# Decoupling.net
KiCad netlist of a schematic drawn in Altium Designer
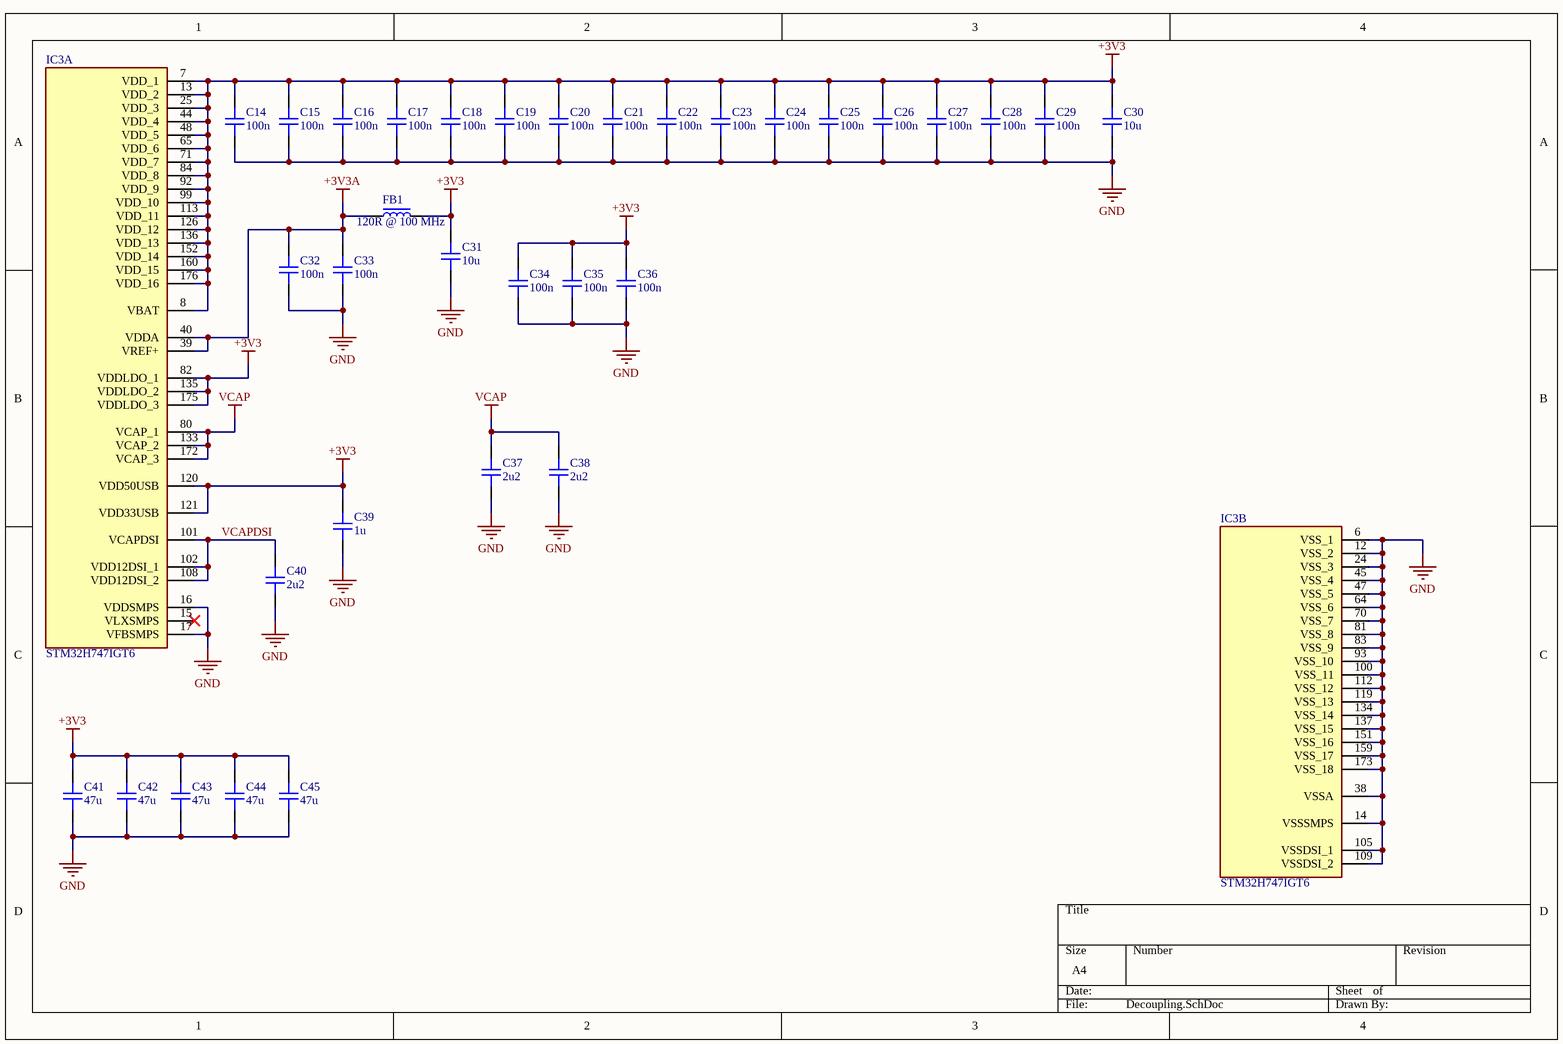
[diagram p0: Decoupling.SchDoc]

(export (version "E")
  (design (tool "Eeschema 10.0.6"))
  (components
    (comp (ref "C14")
      (value "100n")
      (footprint "CAP_0402")
      (description "Capacitor SMD 0402")
      (libsource (lib "Schematic-Lib-PhilsLab") (part "CAP_0402"))
    )
    (comp (ref "C15")
      (value "100n")
      (footprint "CAP_0402")
      (description "Capacitor SMD 0402")
      (libsource (lib "Schematic-Lib-PhilsLab") (part "CAP_0402"))
    )
    (comp (ref "C16")
      (value "100n")
      (footprint "CAP_0402")
      (description "Capacitor SMD 0402")
      (libsource (lib "Schematic-Lib-PhilsLab") (part "CAP_0402"))
    )
    (comp (ref "C17")
      (value "100n")
      (footprint "CAP_0402")
      (description "Capacitor SMD 0402")
      (libsource (lib "Schematic-Lib-PhilsLab") (part "CAP_0402"))
    )
    (comp (ref "C18")
      (value "100n")
      (footprint "CAP_0402")
      (description "Capacitor SMD 0402")
      (libsource (lib "Schematic-Lib-PhilsLab") (part "CAP_0402"))
    )
    (comp (ref "C19")
      (value "100n")
      (footprint "CAP_0402")
      (description "Capacitor SMD 0402")
      (libsource (lib "Schematic-Lib-PhilsLab") (part "CAP_0402"))
    )
    (comp (ref "C20")
      (value "100n")
      (footprint "CAP_0402")
      (description "Capacitor SMD 0402")
      (libsource (lib "Schematic-Lib-PhilsLab") (part "CAP_0402"))
    )
    (comp (ref "C21")
      (value "100n")
      (footprint "CAP_0402")
      (description "Capacitor SMD 0402")
      (libsource (lib "Schematic-Lib-PhilsLab") (part "CAP_0402"))
    )
    (comp (ref "C22")
      (value "100n")
      (footprint "CAP_0402")
      (description "Capacitor SMD 0402")
      (libsource (lib "Schematic-Lib-PhilsLab") (part "CAP_0402"))
    )
    (comp (ref "C23")
      (value "100n")
      (footprint "CAP_0402")
      (description "Capacitor SMD 0402")
      (libsource (lib "Schematic-Lib-PhilsLab") (part "CAP_0402"))
    )
    (comp (ref "C24")
      (value "100n")
      (footprint "CAP_0402")
      (description "Capacitor SMD 0402")
      (libsource (lib "Schematic-Lib-PhilsLab") (part "CAP_0402"))
    )
    (comp (ref "C25")
      (value "100n")
      (footprint "CAP_0402")
      (description "Capacitor SMD 0402")
      (libsource (lib "Schematic-Lib-PhilsLab") (part "CAP_0402"))
    )
    (comp (ref "C26")
      (value "100n")
      (footprint "CAP_0402")
      (description "Capacitor SMD 0402")
      (libsource (lib "Schematic-Lib-PhilsLab") (part "CAP_0402"))
    )
    (comp (ref "C27")
      (value "100n")
      (footprint "CAP_0402")
      (description "Capacitor SMD 0402")
      (libsource (lib "Schematic-Lib-PhilsLab") (part "CAP_0402"))
    )
    (comp (ref "C28")
      (value "100n")
      (footprint "CAP_0402")
      (description "Capacitor SMD 0402")
      (libsource (lib "Schematic-Lib-PhilsLab") (part "CAP_0402"))
    )
    (comp (ref "C29")
      (value "100n")
      (footprint "CAP_0402")
      (description "Capacitor SMD 0402")
      (libsource (lib "Schematic-Lib-PhilsLab") (part "CAP_0402"))
    )
    (comp (ref "C30")
      (value "10u")
      (footprint "CAP_0603")
      (description "Capacitor SMD 0603")
      (libsource (lib "Schematic-Lib-PhilsLab") (part "CAP_0603"))
    )
    (comp (ref "C31")
      (value "10u")
      (footprint "CAP_0603")
      (description "Capacitor SMD 0603")
      (libsource (lib "Schematic-Lib-PhilsLab") (part "CAP_0603"))
    )
    (comp (ref "C32")
      (value "100n")
      (footprint "CAP_0402")
      (description "Capacitor SMD 0402")
      (libsource (lib "Schematic-Lib-PhilsLab") (part "CAP_0402"))
    )
    (comp (ref "C33")
      (value "100n")
      (footprint "CAP_0402")
      (description "Capacitor SMD 0402")
      (libsource (lib "Schematic-Lib-PhilsLab") (part "CAP_0402"))
    )
    (comp (ref "C34")
      (value "100n")
      (footprint "CAP_0402")
      (description "Capacitor SMD 0402")
      (libsource (lib "Schematic-Lib-PhilsLab") (part "CAP_0402"))
    )
    (comp (ref "C35")
      (value "100n")
      (footprint "CAP_0402")
      (description "Capacitor SMD 0402")
      (libsource (lib "Schematic-Lib-PhilsLab") (part "CAP_0402"))
    )
    (comp (ref "C36")
      (value "100n")
      (footprint "CAP_0402")
      (description "Capacitor SMD 0402")
      (libsource (lib "Schematic-Lib-PhilsLab") (part "CAP_0402"))
    )
    (comp (ref "C37")
      (value "2u2")
      (footprint "CAP_0402")
      (description "Capacitor SMD 0402")
      (libsource (lib "Schematic-Lib-PhilsLab") (part "CAP_0402"))
    )
    (comp (ref "C38")
      (value "2u2")
      (footprint "CAP_0402")
      (description "Capacitor SMD 0402")
      (libsource (lib "Schematic-Lib-PhilsLab") (part "CAP_0402"))
    )
    (comp (ref "C39")
      (value "1u")
      (footprint "CAP_0402")
      (description "Capacitor SMD 0402")
      (libsource (lib "Schematic-Lib-PhilsLab") (part "CAP_0402"))
    )
    (comp (ref "C40")
      (value "2u2")
      (footprint "CAP_0402")
      (description "Capacitor SMD 0402")
      (libsource (lib "Schematic-Lib-PhilsLab") (part "CAP_0402"))
    )
    (comp (ref "C41")
      (value "47u")
      (footprint "CAP_1210")
      (description "Capacitor SMD 1210")
      (libsource (lib "Schematic-Lib-PhilsLab") (part "CAP_1210"))
    )
    (comp (ref "C42")
      (value "47u")
      (footprint "CAP_1210")
      (description "Capacitor SMD 1210")
      (libsource (lib "Schematic-Lib-PhilsLab") (part "CAP_1210"))
    )
    (comp (ref "C43")
      (value "47u")
      (footprint "CAP_1210")
      (description "Capacitor SMD 1210")
      (libsource (lib "Schematic-Lib-PhilsLab") (part "CAP_1210"))
    )
    (comp (ref "C44")
      (value "47u")
      (footprint "CAP_1210")
      (description "Capacitor SMD 1210")
      (libsource (lib "Schematic-Lib-PhilsLab") (part "CAP_1210"))
    )
    (comp (ref "C45")
      (value "47u")
      (footprint "CAP_1210")
      (description "Capacitor SMD 1210")
      (libsource (lib "Schematic-Lib-PhilsLab") (part "CAP_1210"))
    )
    (comp (ref "FB1")
      (value "120R @ 100 MHz")
      (footprint "FB_0402")
      (description "Ferrite Bead SMD 0402")
      (libsource (lib "Schematic-Lib-PhilsLab") (part "FB_0402"))
    )
    (comp (ref "IC3")
      (value "STM32H747IGT6")
      (footprint "Footprint-Lib-PhilsLab:QFP50P2600X2600X160-176N")
      (description "Integrated Circuit")
      (fields (field (name "MOUSER PART NUMBER") "511-STM32H747IGT6"))
      (libsource (lib "Schematic-Lib-PhilsLab") (part "STM32H747IGT6"))
    )
  )
  (nets
    (net (code "1") (name "+3V3") (class "Default")
      (node (ref "C14") (pin "2") (pinfunction "2_2") (pintype "passive"))
      (node (ref "C15") (pin "2") (pinfunction "2_2") (pintype "passive"))
      (node (ref "C16") (pin "2") (pinfunction "2_2") (pintype "passive"))
      (node (ref "C17") (pin "2") (pinfunction "2_2") (pintype "passive"))
      (node (ref "C18") (pin "2") (pinfunction "2_2") (pintype "passive"))
      (node (ref "C19") (pin "2") (pinfunction "2_2") (pintype "passive"))
      (node (ref "C20") (pin "2") (pinfunction "2_2") (pintype "passive"))
      (node (ref "C21") (pin "2") (pinfunction "2_2") (pintype "passive"))
      (node (ref "C22") (pin "2") (pinfunction "2_2") (pintype "passive"))
      (node (ref "C23") (pin "2") (pinfunction "2_2") (pintype "passive"))
      (node (ref "C24") (pin "2") (pinfunction "2_2") (pintype "passive"))
      (node (ref "C25") (pin "2") (pinfunction "2_2") (pintype "passive"))
      (node (ref "C26") (pin "2") (pinfunction "2_2") (pintype "passive"))
      (node (ref "C27") (pin "2") (pinfunction "2_2") (pintype "passive"))
      (node (ref "C28") (pin "2") (pinfunction "2_2") (pintype "passive"))
      (node (ref "C29") (pin "2") (pinfunction "2_2") (pintype "passive"))
      (node (ref "C30") (pin "2") (pinfunction "2_2") (pintype "passive"))
      (node (ref "C31") (pin "2") (pinfunction "2_2") (pintype "passive"))
      (node (ref "C34") (pin "2") (pinfunction "2_2") (pintype "passive"))
      (node (ref "C35") (pin "2") (pinfunction "2_2") (pintype "passive"))
      (node (ref "C36") (pin "2") (pinfunction "2_2") (pintype "passive"))
      (node (ref "C39") (pin "2") (pinfunction "2_2") (pintype "passive"))
      (node (ref "C41") (pin "2") (pinfunction "2_2") (pintype "passive"))
      (node (ref "C42") (pin "2") (pinfunction "2_2") (pintype "passive"))
      (node (ref "C43") (pin "2") (pinfunction "2_2") (pintype "passive"))
      (node (ref "C44") (pin "2") (pinfunction "2_2") (pintype "passive"))
      (node (ref "C45") (pin "2") (pinfunction "2_2") (pintype "passive"))
      (node (ref "FB1") (pin "2") (pinfunction "2_2") (pintype "passive"))
      (node (ref "IC3") (pin "113") (pinfunction "VDD_11_113") (pintype "passive"))
      (node (ref "IC3") (pin "120") (pinfunction "VDD50USB_120") (pintype "passive"))
      (node (ref "IC3") (pin "121") (pinfunction "VDD33USB_121") (pintype "passive"))
      (node (ref "IC3") (pin "126") (pinfunction "VDD_12_126") (pintype "passive"))
      (node (ref "IC3") (pin "13") (pinfunction "VDD_2_13") (pintype "passive"))
      (node (ref "IC3") (pin "135") (pinfunction "VDDLDO_2_135") (pintype "passive"))
      (node (ref "IC3") (pin "136") (pinfunction "VDD_13_136") (pintype "passive"))
      (node (ref "IC3") (pin "152") (pinfunction "VDD_14_152") (pintype "passive"))
      (node (ref "IC3") (pin "160") (pinfunction "VDD_15_160") (pintype "passive"))
      (node (ref "IC3") (pin "175") (pinfunction "VDDLDO_3_175") (pintype "passive"))
      (node (ref "IC3") (pin "176") (pinfunction "VDD_16_176") (pintype "passive"))
      (node (ref "IC3") (pin "25") (pinfunction "VDD_3_25") (pintype "passive"))
      (node (ref "IC3") (pin "44") (pinfunction "VDD_4_44") (pintype "passive"))
      (node (ref "IC3") (pin "48") (pinfunction "VDD_5_48") (pintype "passive"))
      (node (ref "IC3") (pin "65") (pinfunction "VDD_6_65") (pintype "passive"))
      (node (ref "IC3") (pin "7") (pinfunction "VDD_1_7") (pintype "passive"))
      (node (ref "IC3") (pin "71") (pinfunction "VDD_7_71") (pintype "passive"))
      (node (ref "IC3") (pin "8") (pinfunction "VBAT_8") (pintype "passive"))
      (node (ref "IC3") (pin "82") (pinfunction "VDDLDO_1_82") (pintype "passive"))
      (node (ref "IC3") (pin "84") (pinfunction "VDD_8_84") (pintype "passive"))
      (node (ref "IC3") (pin "92") (pinfunction "VDD_9_92") (pintype "passive"))
      (node (ref "IC3") (pin "99") (pinfunction "VDD_10_99") (pintype "passive"))
    )
    (net (code "2") (name "+3V3A") (class "Default")
      (node (ref "C32") (pin "2") (pinfunction "2_2") (pintype "passive"))
      (node (ref "C33") (pin "2") (pinfunction "2_2") (pintype "passive"))
      (node (ref "FB1") (pin "1") (pinfunction "1_1") (pintype "passive"))
      (node (ref "IC3") (pin "39") (pinfunction "VREF+_39") (pintype "passive"))
      (node (ref "IC3") (pin "40") (pinfunction "VDDA_40") (pintype "passive"))
    )
    (net (code "3") (name "/VCAPDSI") (class "Default")
      (node (ref "C40") (pin "2") (pinfunction "2_2") (pintype "passive"))
      (node (ref "IC3") (pin "101") (pinfunction "VCAPDSI_101") (pintype "passive"))
      (node (ref "IC3") (pin "102") (pinfunction "VDD12DSI_1_102") (pintype "passive"))
      (node (ref "IC3") (pin "108") (pinfunction "VDD12DSI_2_108") (pintype "passive"))
    )
    (net (code "4") (name "GND") (class "Default")
      (node (ref "C14") (pin "1") (pinfunction "1_1") (pintype "passive"))
      (node (ref "C15") (pin "1") (pinfunction "1_1") (pintype "passive"))
      (node (ref "C16") (pin "1") (pinfunction "1_1") (pintype "passive"))
      (node (ref "C17") (pin "1") (pinfunction "1_1") (pintype "passive"))
      (node (ref "C18") (pin "1") (pinfunction "1_1") (pintype "passive"))
      (node (ref "C19") (pin "1") (pinfunction "1_1") (pintype "passive"))
      (node (ref "C20") (pin "1") (pinfunction "1_1") (pintype "passive"))
      (node (ref "C21") (pin "1") (pinfunction "1_1") (pintype "passive"))
      (node (ref "C22") (pin "1") (pinfunction "1_1") (pintype "passive"))
      (node (ref "C23") (pin "1") (pinfunction "1_1") (pintype "passive"))
      (node (ref "C24") (pin "1") (pinfunction "1_1") (pintype "passive"))
      (node (ref "C25") (pin "1") (pinfunction "1_1") (pintype "passive"))
      (node (ref "C26") (pin "1") (pinfunction "1_1") (pintype "passive"))
      (node (ref "C27") (pin "1") (pinfunction "1_1") (pintype "passive"))
      (node (ref "C28") (pin "1") (pinfunction "1_1") (pintype "passive"))
      (node (ref "C29") (pin "1") (pinfunction "1_1") (pintype "passive"))
      (node (ref "C30") (pin "1") (pinfunction "1_1") (pintype "passive"))
      (node (ref "C31") (pin "1") (pinfunction "1_1") (pintype "passive"))
      (node (ref "C32") (pin "1") (pinfunction "1_1") (pintype "passive"))
      (node (ref "C33") (pin "1") (pinfunction "1_1") (pintype "passive"))
      (node (ref "C34") (pin "1") (pinfunction "1_1") (pintype "passive"))
      (node (ref "C35") (pin "1") (pinfunction "1_1") (pintype "passive"))
      (node (ref "C36") (pin "1") (pinfunction "1_1") (pintype "passive"))
      (node (ref "C37") (pin "1") (pinfunction "1_1") (pintype "passive"))
      (node (ref "C38") (pin "1") (pinfunction "1_1") (pintype "passive"))
      (node (ref "C39") (pin "1") (pinfunction "1_1") (pintype "passive"))
      (node (ref "C40") (pin "1") (pinfunction "1_1") (pintype "passive"))
      (node (ref "C41") (pin "1") (pinfunction "1_1") (pintype "passive"))
      (node (ref "C42") (pin "1") (pinfunction "1_1") (pintype "passive"))
      (node (ref "C43") (pin "1") (pinfunction "1_1") (pintype "passive"))
      (node (ref "C44") (pin "1") (pinfunction "1_1") (pintype "passive"))
      (node (ref "C45") (pin "1") (pinfunction "1_1") (pintype "passive"))
      (node (ref "IC3") (pin "100") (pinfunction "VSS_11_100") (pintype "passive"))
      (node (ref "IC3") (pin "105") (pinfunction "VSSDSI_1_105") (pintype "passive"))
      (node (ref "IC3") (pin "109") (pinfunction "VSSDSI_2_109") (pintype "passive"))
      (node (ref "IC3") (pin "112") (pinfunction "VSS_12_112") (pintype "passive"))
      (node (ref "IC3") (pin "119") (pinfunction "VSS_13_119") (pintype "passive"))
      (node (ref "IC3") (pin "12") (pinfunction "VSS_2_12") (pintype "passive"))
      (node (ref "IC3") (pin "134") (pinfunction "VSS_14_134") (pintype "passive"))
      (node (ref "IC3") (pin "137") (pinfunction "VSS_15_137") (pintype "passive"))
      (node (ref "IC3") (pin "14") (pinfunction "VSSSMPS_14") (pintype "passive"))
      (node (ref "IC3") (pin "151") (pinfunction "VSS_16_151") (pintype "passive"))
      (node (ref "IC3") (pin "159") (pinfunction "VSS_17_159") (pintype "passive"))
      (node (ref "IC3") (pin "16") (pinfunction "VDDSMPS_16") (pintype "passive"))
      (node (ref "IC3") (pin "17") (pinfunction "VFBSMPS_17") (pintype "passive"))
      (node (ref "IC3") (pin "173") (pinfunction "VSS_18_173") (pintype "passive"))
      (node (ref "IC3") (pin "24") (pinfunction "VSS_3_24") (pintype "passive"))
      (node (ref "IC3") (pin "38") (pinfunction "VSSA_38") (pintype "passive"))
      (node (ref "IC3") (pin "45") (pinfunction "VSS_4_45") (pintype "passive"))
      (node (ref "IC3") (pin "47") (pinfunction "VSS_5_47") (pintype "passive"))
      (node (ref "IC3") (pin "6") (pinfunction "VSS_1_6") (pintype "passive"))
      (node (ref "IC3") (pin "64") (pinfunction "VSS_6_64") (pintype "passive"))
      (node (ref "IC3") (pin "70") (pinfunction "VSS_7_70") (pintype "passive"))
      (node (ref "IC3") (pin "81") (pinfunction "VSS_8_81") (pintype "passive"))
      (node (ref "IC3") (pin "83") (pinfunction "VSS_9_83") (pintype "passive"))
      (node (ref "IC3") (pin "93") (pinfunction "VSS_10_93") (pintype "passive"))
    )
    (net (code "5") (name "VCAP") (class "Default")
      (node (ref "C37") (pin "2") (pinfunction "2_2") (pintype "passive"))
      (node (ref "C38") (pin "2") (pinfunction "2_2") (pintype "passive"))
      (node (ref "IC3") (pin "133") (pinfunction "VCAP_2_133") (pintype "passive"))
      (node (ref "IC3") (pin "172") (pinfunction "VCAP_3_172") (pintype "passive"))
      (node (ref "IC3") (pin "80") (pinfunction "VCAP_1_80") (pintype "passive"))
    )
    (net (code "6") (name "unconnected-(IC3A-VLXSMPS-Pad15)") (class "Default")
      (node (ref "IC3") (pin "15") (pinfunction "VLXSMPS_15") (pintype "passive+no_connect"))
    )
  )
)
